# atmega2560_2_sch.net
KiCad netlist of a schematic drawn in Altium Designer
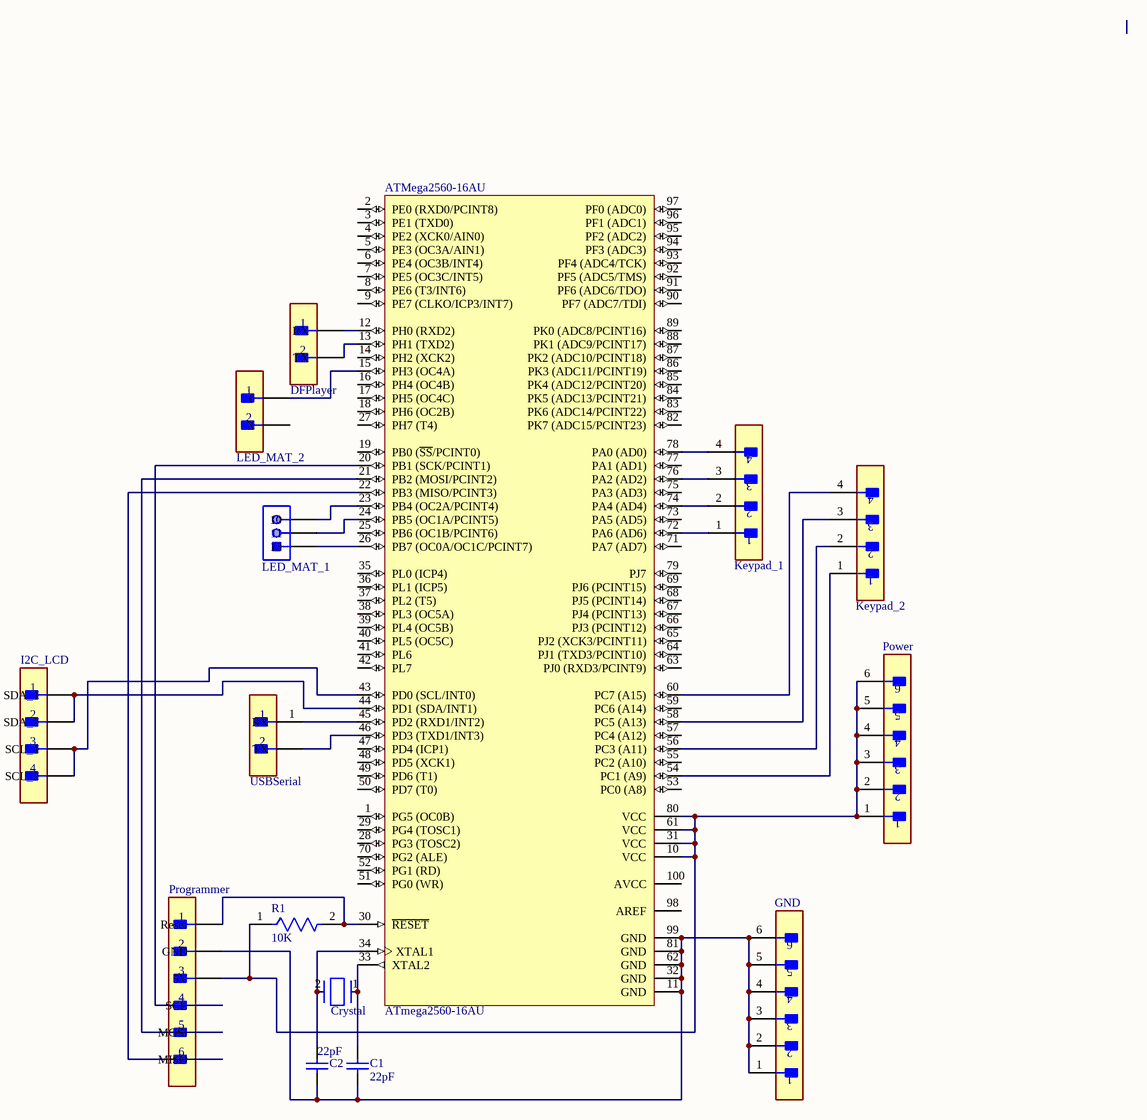
[diagram p0: atmega2560_2_sch.SchDoc]

(export (version "E")
  (design (tool "Eeschema 10.0.6"))
  (components
    (comp (ref "ATMega2560-16AU")
      (value "ATmega2560-16AU")
      (footprint "100A_M")
      (libsource (lib "Altium Content Vault") (part "MC-8B-ATM640-SQ100"))
    )
    (comp (ref "C1")
      (value "22pF")
      (footprint "KEMT-C315-THT-2")
      (description "Capacitor, Ceramic, 22 pF, +/-10 %, 100 V, -55 to 125 degC, 2-Pin THD, RoHS, Bulk")
      (libsource (lib "Altium Content Vault") (part "CAP-NP-2"))
    )
    (comp (ref "C2")
      (value "22pF")
      (footprint "KEMT-C315-THT-2")
      (description "Capacitor, Ceramic, 22 pF, +/-10 %, 100 V, -55 to 125 degC, 2-Pin THD, RoHS, Bulk")
      (libsource (lib "Altium Content Vault") (part "CAP-NP-2"))
    )
    (comp (ref "Crystal")
      (value "ABLS-16.000MHZ-K4T")
      (footprint "FP-ABLS-MFG")
      (description "CRYSTAL 16.0000MHZ 18PF SMD")
      (fields
        (field (name "TOLERANCE") "30ppm")
        (field (name "OCTOPART") "https://octopart.com/abls-16.000mhz-k4t-abracon-18618626")
      )
      (libsource (lib "Altium Content Vault") (part "c23a69dc6c9e2f18f2079038eb95dd1"))
    )
    (comp (ref "DFPlayer")
      (value "M20-9990246")
      (footprint "FP-M20-9990246-MFG")
      (description "CONN HEADER VERT 2POS 2.54MM")
      (fields
        (field (name "OCTOPART") "https://octopart.com/m20-9990246-harwin-2590635")
        (field (name "MANUFACTURER") "Harwin")
      )
      (libsource (lib "Altium Content Vault") (part "3bc925449376181038e59eaffc5286c"))
    )
    (comp (ref "GND")
      (value "22-04-1061")
      (footprint "FP-22-04-1061-MFG")
      (description "CONN HEADER VERT 6POS 2.5MM")
      (libsource (lib "") (part "f2cb566baf1c37ab5a3b8e90bbeafd6_1"))
    )
    (comp (ref "I2C_LCD")
      (value "B4B-XH-A(LF)(SN)")
      (footprint "FP-B4B-XH-A_LF_SN-MFG")
      (description "CONN HEADER VERT 4POS 2.5MM")
      (libsource (lib "Altium Content Vault") (part "299a8cea1bdcbc3624fe62c390fa72c"))
    )
    (comp (ref "Keypad_1")
      (value "B4B-XH-A(LF)(SN)")
      (footprint "FP-B4B-XH-A_LF_SN-MFG")
      (description "CONN HEADER VERT 4POS 2.5MM")
      (libsource (lib "") (part "299a8cea1bdcbc3624fe62c390fa72c_1"))
    )
    (comp (ref "Keypad_2")
      (value "B4B-XH-A(LF)(SN)")
      (footprint "FP-B4B-XH-A_LF_SN-MFG")
      (description "CONN HEADER VERT 4POS 2.5MM")
      (libsource (lib "") (part "299a8cea1bdcbc3624fe62c390fa72c_1"))
    )
    (comp (ref "LED_MAT_1")
      (value "B3P-VH(LF)(SN)")
      (footprint "JST-B3P-VH(LF)(SN)-3_V")
      (libsource (lib "Altium Content Vault") (part "CN-1P-M-R3"))
    )
    (comp (ref "LED_MAT_2")
      (value "M20-9990246")
      (footprint "FP-M20-9990246-MFG")
      (description "CONN HEADER VERT 2POS 2.54MM")
      (fields
        (field (name "OCTOPART") "https://octopart.com/m20-9990246-harwin-2590635")
        (field (name "MANUFACTURER") "Harwin")
      )
      (libsource (lib "Altium Content Vault") (part "3bc925449376181038e59eaffc5286c"))
    )
    (comp (ref "Power")
      (value "22-04-1061")
      (footprint "FP-22-04-1061-MFG")
      (description "CONN HEADER VERT 6POS 2.5MM")
      (libsource (lib "") (part "f2cb566baf1c37ab5a3b8e90bbeafd6_1"))
    )
    (comp (ref "Programmer")
      (value "22-29-2061")
      (footprint "FP-22-29-2061-MFG")
      (description "CONN HEADER VERT 6POS 2.54MM")
      (libsource (lib "Altium Content Vault") (part "f2cb566baf1c37ab5a3b8e90bbeafd6"))
    )
    (comp (ref "R1")
      (value "10K")
      (footprint "FP-MBB0207-MFG")
      (description "RES 10K OHM 0.6W 1% AXIAL")
      (fields (field (name "TOLERANCE") "1%"))
      (libsource (lib "Altium Content Vault") (part "1029c3af85768c4190bb7ad29bc67b5"))
    )
    (comp (ref "USBSerial")
      (value "M20-9990246")
      (footprint "FP-M20-9990246-MFG")
      (description "CONN HEADER VERT 2POS 2.54MM")
      (fields
        (field (name "OCTOPART") "https://octopart.com/m20-9990246-harwin-2590635")
        (field (name "MANUFACTURER") "Harwin")
      )
      (libsource (lib "") (part "3bc925449376181038e59eaffc5286c_1"))
    )
  )
  (nets
    (net (code "1") (name "Net-(ATMega2560-16AU-PA0_(AD0))") (class "Default")
      (node (ref "ATMega2560-16AU") (pin "78") (pinfunction "PA0_(AD0)_78") (pintype "bidirectional"))
      (node (ref "Keypad_1") (pin "4") (pinfunction "4_4") (pintype "passive"))
    )
    (net (code "2") (name "Net-(ATMega2560-16AU-PA2_(AD2))") (class "Default")
      (node (ref "ATMega2560-16AU") (pin "76") (pinfunction "PA2_(AD2)_76") (pintype "bidirectional"))
      (node (ref "Keypad_1") (pin "3") (pinfunction "3_3") (pintype "passive"))
    )
    (net (code "3") (name "Net-(ATMega2560-16AU-PA4_(AD4))") (class "Default")
      (node (ref "ATMega2560-16AU") (pin "74") (pinfunction "PA4_(AD4)_74") (pintype "bidirectional"))
      (node (ref "Keypad_1") (pin "2") (pinfunction "2_2") (pintype "passive"))
    )
    (net (code "4") (name "Net-(ATMega2560-16AU-PA6_(AD6))") (class "Default")
      (node (ref "ATMega2560-16AU") (pin "72") (pinfunction "PA6_(AD6)_72") (pintype "bidirectional"))
      (node (ref "Keypad_1") (pin "1") (pinfunction "1_1") (pintype "passive"))
    )
    (net (code "5") (name "Net-(ATMega2560-16AU-PB1_(SCK{slash}PCINT1))") (class "Default")
      (node (ref "ATMega2560-16AU") (pin "20") (pinfunction "PB1_(SCK/PCINT1)_20") (pintype "bidirectional"))
      (node (ref "Programmer") (pin "4") (pinfunction "SCL_4") (pintype "passive"))
    )
    (net (code "6") (name "Net-(ATMega2560-16AU-PB2_(MOSI{slash}PCINT2))") (class "Default")
      (node (ref "ATMega2560-16AU") (pin "21") (pinfunction "PB2_(MOSI/PCINT2)_21") (pintype "bidirectional"))
      (node (ref "Programmer") (pin "5") (pinfunction "MOSI_5") (pintype "passive"))
    )
    (net (code "7") (name "Net-(ATMega2560-16AU-PB3_(MISO{slash}PCINT3))") (class "Default")
      (node (ref "ATMega2560-16AU") (pin "22") (pinfunction "PB3_(MISO/PCINT3)_22") (pintype "bidirectional"))
      (node (ref "Programmer") (pin "6") (pinfunction "MISO_6") (pintype "passive"))
    )
    (net (code "8") (name "Net-(ATMega2560-16AU-PB4_(OC2A{slash}PCINT4))") (class "Default")
      (node (ref "ATMega2560-16AU") (pin "23") (pinfunction "PB4_(OC2A/PCINT4)_23") (pintype "bidirectional"))
      (node (ref "LED_MAT_1") (pin "3") (pinfunction "10_3") (pintype "passive"))
    )
    (net (code "9") (name "Net-(ATMega2560-16AU-PB5_(OC1A{slash}PCINT5))") (class "Default")
      (node (ref "ATMega2560-16AU") (pin "24") (pinfunction "PB5_(OC1A/PCINT5)_24") (pintype "bidirectional"))
      (node (ref "LED_MAT_1") (pin "2") (pinfunction "11_2") (pintype "passive"))
    )
    (net (code "10") (name "Net-(ATMega2560-16AU-PB7_(OC0A{slash}OC1C{slash}PCINT7))") (class "Default")
      (node (ref "ATMega2560-16AU") (pin "26") (pinfunction "PB7_(OC0A/OC1C/PCINT7)_26") (pintype "bidirectional"))
      (node (ref "LED_MAT_1") (pin "1") (pinfunction "13_1") (pintype "passive"))
    )
    (net (code "11") (name "Net-(ATMega2560-16AU-PC1_(A9))") (class "Default")
      (node (ref "ATMega2560-16AU") (pin "54") (pinfunction "PC1_(A9)_54") (pintype "bidirectional"))
      (node (ref "Keypad_2") (pin "1") (pinfunction "1_1") (pintype "passive"))
    )
    (net (code "12") (name "Net-(ATMega2560-16AU-PC3_(A11))") (class "Default")
      (node (ref "ATMega2560-16AU") (pin "56") (pinfunction "PC3_(A11)_56") (pintype "bidirectional"))
      (node (ref "Keypad_2") (pin "2") (pinfunction "2_2") (pintype "passive"))
    )
    (net (code "13") (name "Net-(ATMega2560-16AU-PC5_(A13))") (class "Default")
      (node (ref "ATMega2560-16AU") (pin "58") (pinfunction "PC5_(A13)_58") (pintype "bidirectional"))
      (node (ref "Keypad_2") (pin "3") (pinfunction "3_3") (pintype "passive"))
    )
    (net (code "14") (name "Net-(ATMega2560-16AU-PC7_(A15))") (class "Default")
      (node (ref "ATMega2560-16AU") (pin "60") (pinfunction "PC7_(A15)_60") (pintype "bidirectional"))
      (node (ref "Keypad_2") (pin "4") (pinfunction "4_4") (pintype "passive"))
    )
    (net (code "15") (name "Net-(ATMega2560-16AU-PD0_(SCL{slash}INT0))") (class "Default")
      (node (ref "ATMega2560-16AU") (pin "43") (pinfunction "PD0_(SCL/INT0)_43") (pintype "bidirectional"))
      (node (ref "I2C_LCD") (pin "3") (pinfunction "SCL_1_3") (pintype "passive"))
      (node (ref "I2C_LCD") (pin "4") (pinfunction "SCL_2_4") (pintype "passive"))
    )
    (net (code "16") (name "Net-(ATMega2560-16AU-PD1_(SDA{slash}INT1))") (class "Default")
      (node (ref "ATMega2560-16AU") (pin "44") (pinfunction "PD1_(SDA/INT1)_44") (pintype "bidirectional"))
      (node (ref "I2C_LCD") (pin "1") (pinfunction "SDA_1_1") (pintype "passive"))
      (node (ref "I2C_LCD") (pin "2") (pinfunction "SDA_2_2") (pintype "passive"))
    )
    (net (code "17") (name "Net-(ATMega2560-16AU-PD2_(RXD1{slash}INT2))") (class "Default")
      (node (ref "ATMega2560-16AU") (pin "45") (pinfunction "PD2_(RXD1/INT2)_45") (pintype "bidirectional"))
      (node (ref "USBSerial") (pin "1") (pinfunction "RX_1") (pintype "passive"))
    )
    (net (code "18") (name "Net-(ATMega2560-16AU-PD3_(TXD1{slash}INT3))") (class "Default")
      (node (ref "ATMega2560-16AU") (pin "46") (pinfunction "PD3_(TXD1/INT3)_46") (pintype "bidirectional"))
      (node (ref "USBSerial") (pin "2") (pinfunction "TX_2") (pintype "passive"))
    )
    (net (code "19") (name "Net-(ATMega2560-16AU-PH0_(RXD2))") (class "Default")
      (node (ref "ATMega2560-16AU") (pin "12") (pinfunction "PH0_(RXD2)_12") (pintype "bidirectional"))
      (node (ref "DFPlayer") (pin "1") (pinfunction "RX_1") (pintype "passive"))
    )
    (net (code "20") (name "Net-(ATMega2560-16AU-PH1_(TXD2))") (class "Default")
      (node (ref "ATMega2560-16AU") (pin "13") (pinfunction "PH1_(TXD2)_13") (pintype "bidirectional"))
      (node (ref "DFPlayer") (pin "2") (pinfunction "TX_2") (pintype "passive"))
    )
    (net (code "21") (name "Net-(ATMega2560-16AU-PH3_(OC4A))") (class "Default")
      (node (ref "ATMega2560-16AU") (pin "15") (pinfunction "PH3_(OC4A)_15") (pintype "bidirectional"))
      (node (ref "LED_MAT_2") (pin "1") (pinfunction "RX_1") (pintype "passive"))
    )
    (net (code "22") (name "Net-(ATMega2560-16AU-XTAL1)") (class "Default")
      (node (ref "ATMega2560-16AU") (pin "34") (pinfunction "XTAL1_34") (pintype "input"))
      (node (ref "C2") (pin "2") (pinfunction "2_2") (pintype "passive"))
      (node (ref "Crystal") (pin "2") (pinfunction "2_2") (pintype "passive"))
    )
    (net (code "23") (name "Net-(ATMega2560-16AU-XTAL2)") (class "Default")
      (node (ref "ATMega2560-16AU") (pin "33") (pinfunction "XTAL2_33") (pintype "output"))
      (node (ref "C1") (pin "2") (pinfunction "2_2") (pintype "passive"))
      (node (ref "Crystal") (pin "1") (pinfunction "1_1") (pintype "passive"))
    )
    (net (code "24") (name "Net-(ATMega2560-16AU-~{RESET})") (class "Default")
      (node (ref "ATMega2560-16AU") (pin "30") (pinfunction "~{RESET}_30") (pintype "input"))
      (node (ref "Programmer") (pin "1") (pinfunction "Reset_1") (pintype "passive"))
      (node (ref "R1") (pin "2") (pinfunction "2_2") (pintype "passive"))
    )
    (net (code "25") (name "Net-(Programmer-5V)") (class "Default")
      (node (ref "ATMega2560-16AU") (pin "10") (pinfunction "VCC_10") (pintype "power_in"))
      (node (ref "ATMega2560-16AU") (pin "31") (pinfunction "VCC_31") (pintype "power_in"))
      (node (ref "ATMega2560-16AU") (pin "61") (pinfunction "VCC_61") (pintype "power_in"))
      (node (ref "ATMega2560-16AU") (pin "80") (pinfunction "VCC_80") (pintype "power_in"))
      (node (ref "Power") (pin "1") (pinfunction "1_1") (pintype "passive"))
      (node (ref "Power") (pin "2") (pinfunction "2_2") (pintype "passive"))
      (node (ref "Power") (pin "3") (pinfunction "3_3") (pintype "passive"))
      (node (ref "Power") (pin "4") (pinfunction "4_4") (pintype "passive"))
      (node (ref "Power") (pin "5") (pinfunction "5_5") (pintype "passive"))
      (node (ref "Power") (pin "6") (pinfunction "6_6") (pintype "passive"))
      (node (ref "Programmer") (pin "3") (pinfunction "5V_3") (pintype "passive"))
      (node (ref "R1") (pin "1") (pinfunction "1_1") (pintype "passive"))
    )
    (net (code "26") (name "Net-(Programmer-GND)") (class "Default")
      (node (ref "ATMega2560-16AU") (pin "11") (pinfunction "GND_11") (pintype "power_in"))
      (node (ref "ATMega2560-16AU") (pin "32") (pinfunction "GND_32") (pintype "power_in"))
      (node (ref "ATMega2560-16AU") (pin "62") (pinfunction "GND_62") (pintype "power_in"))
      (node (ref "ATMega2560-16AU") (pin "81") (pinfunction "GND_81") (pintype "power_in"))
      (node (ref "ATMega2560-16AU") (pin "99") (pinfunction "GND_99") (pintype "power_in"))
      (node (ref "C1") (pin "1") (pinfunction "1_1") (pintype "passive"))
      (node (ref "C2") (pin "1") (pinfunction "1_1") (pintype "passive"))
      (node (ref "GND") (pin "1") (pinfunction "1_1") (pintype "passive"))
      (node (ref "GND") (pin "2") (pinfunction "2_2") (pintype "passive"))
      (node (ref "GND") (pin "3") (pinfunction "3_3") (pintype "passive"))
      (node (ref "GND") (pin "4") (pinfunction "4_4") (pintype "passive"))
      (node (ref "GND") (pin "5") (pinfunction "5_5") (pintype "passive"))
      (node (ref "GND") (pin "6") (pinfunction "6_6") (pintype "passive"))
      (node (ref "Programmer") (pin "2") (pinfunction "GND_2") (pintype "passive"))
    )
    (net (code "27") (name "unconnected-(ATMega2560-16AU-AREF-Pad98)") (class "Default")
      (node (ref "ATMega2560-16AU") (pin "98") (pinfunction "AREF_98") (pintype "power_in"))
    )
    (net (code "28") (name "unconnected-(ATMega2560-16AU-AVCC-Pad100)") (class "Default")
      (node (ref "ATMega2560-16AU") (pin "100") (pinfunction "AVCC_100") (pintype "power_in"))
    )
    (net (code "29") (name "unconnected-(ATMega2560-16AU-PA1_(AD1)-Pad77)") (class "Default")
      (node (ref "ATMega2560-16AU") (pin "77") (pinfunction "PA1_(AD1)_77") (pintype "bidirectional"))
    )
    (net (code "30") (name "unconnected-(ATMega2560-16AU-PA3_(AD3)-Pad75)") (class "Default")
      (node (ref "ATMega2560-16AU") (pin "75") (pinfunction "PA3_(AD3)_75") (pintype "bidirectional"))
    )
    (net (code "31") (name "unconnected-(ATMega2560-16AU-PA5_(AD5)-Pad73)") (class "Default")
      (node (ref "ATMega2560-16AU") (pin "73") (pinfunction "PA5_(AD5)_73") (pintype "bidirectional"))
    )
    (net (code "32") (name "unconnected-(ATMega2560-16AU-PA7_(AD7)-Pad71)") (class "Default")
      (node (ref "ATMega2560-16AU") (pin "71") (pinfunction "PA7_(AD7)_71") (pintype "bidirectional"))
    )
    (net (code "33") (name "unconnected-(ATMega2560-16AU-PB0_(~{SS}{slash}PCINT0)-Pad19)") (class "Default")
      (node (ref "ATMega2560-16AU") (pin "19") (pinfunction "PB0_(~{SS}/PCINT0)_19") (pintype "bidirectional"))
    )
    (net (code "34") (name "unconnected-(ATMega2560-16AU-PB6_(OC1B{slash}PCINT6)-Pad25)") (class "Default")
      (node (ref "ATMega2560-16AU") (pin "25") (pinfunction "PB6_(OC1B/PCINT6)_25") (pintype "bidirectional"))
    )
    (net (code "35") (name "unconnected-(ATMega2560-16AU-PC0_(A8)-Pad53)") (class "Default")
      (node (ref "ATMega2560-16AU") (pin "53") (pinfunction "PC0_(A8)_53") (pintype "bidirectional"))
    )
    (net (code "36") (name "unconnected-(ATMega2560-16AU-PC2_(A10)-Pad55)") (class "Default")
      (node (ref "ATMega2560-16AU") (pin "55") (pinfunction "PC2_(A10)_55") (pintype "bidirectional"))
    )
    (net (code "37") (name "unconnected-(ATMega2560-16AU-PC4_(A12)-Pad57)") (class "Default")
      (node (ref "ATMega2560-16AU") (pin "57") (pinfunction "PC4_(A12)_57") (pintype "bidirectional"))
    )
    (net (code "38") (name "unconnected-(ATMega2560-16AU-PC6_(A14)-Pad59)") (class "Default")
      (node (ref "ATMega2560-16AU") (pin "59") (pinfunction "PC6_(A14)_59") (pintype "bidirectional"))
    )
    (net (code "39") (name "unconnected-(ATMega2560-16AU-PD4_(ICP1)-Pad47)") (class "Default")
      (node (ref "ATMega2560-16AU") (pin "47") (pinfunction "PD4_(ICP1)_47") (pintype "bidirectional"))
    )
    (net (code "40") (name "unconnected-(ATMega2560-16AU-PD5_(XCK1)-Pad48)") (class "Default")
      (node (ref "ATMega2560-16AU") (pin "48") (pinfunction "PD5_(XCK1)_48") (pintype "bidirectional"))
    )
    (net (code "41") (name "unconnected-(ATMega2560-16AU-PD6_(T1)-Pad49)") (class "Default")
      (node (ref "ATMega2560-16AU") (pin "49") (pinfunction "PD6_(T1)_49") (pintype "bidirectional"))
    )
    (net (code "42") (name "unconnected-(ATMega2560-16AU-PD7_(T0)-Pad50)") (class "Default")
      (node (ref "ATMega2560-16AU") (pin "50") (pinfunction "PD7_(T0)_50") (pintype "bidirectional"))
    )
    (net (code "43") (name "unconnected-(ATMega2560-16AU-PE0_(RXD0{slash}PCINT8)-Pad2)") (class "Default")
      (node (ref "ATMega2560-16AU") (pin "2") (pinfunction "PE0_(RXD0/PCINT8)_2") (pintype "bidirectional"))
    )
    (net (code "44") (name "unconnected-(ATMega2560-16AU-PE1_(TXD0)-Pad3)") (class "Default")
      (node (ref "ATMega2560-16AU") (pin "3") (pinfunction "PE1_(TXD0)_3") (pintype "bidirectional"))
    )
    (net (code "45") (name "unconnected-(ATMega2560-16AU-PE2_(XCK0{slash}AIN0)-Pad4)") (class "Default")
      (node (ref "ATMega2560-16AU") (pin "4") (pinfunction "PE2_(XCK0/AIN0)_4") (pintype "bidirectional"))
    )
    (net (code "46") (name "unconnected-(ATMega2560-16AU-PE3_(OC3A{slash}AIN1)-Pad5)") (class "Default")
      (node (ref "ATMega2560-16AU") (pin "5") (pinfunction "PE3_(OC3A/AIN1)_5") (pintype "bidirectional"))
    )
    (net (code "47") (name "unconnected-(ATMega2560-16AU-PE4_(OC3B{slash}INT4)-Pad6)") (class "Default")
      (node (ref "ATMega2560-16AU") (pin "6") (pinfunction "PE4_(OC3B/INT4)_6") (pintype "bidirectional"))
    )
    (net (code "48") (name "unconnected-(ATMega2560-16AU-PE5_(OC3C{slash}INT5)-Pad7)") (class "Default")
      (node (ref "ATMega2560-16AU") (pin "7") (pinfunction "PE5_(OC3C/INT5)_7") (pintype "bidirectional"))
    )
    (net (code "49") (name "unconnected-(ATMega2560-16AU-PE6_(T3{slash}INT6)-Pad8)") (class "Default")
      (node (ref "ATMega2560-16AU") (pin "8") (pinfunction "PE6_(T3/INT6)_8") (pintype "bidirectional"))
    )
    (net (code "50") (name "unconnected-(ATMega2560-16AU-PE7_(CLKO{slash}ICP3{slash}INT7)-Pad9)") (class "Default")
      (node (ref "ATMega2560-16AU") (pin "9") (pinfunction "PE7_(CLKO/ICP3/INT7)_9") (pintype "bidirectional"))
    )
    (net (code "51") (name "unconnected-(ATMega2560-16AU-PF0_(ADC0)-Pad97)") (class "Default")
      (node (ref "ATMega2560-16AU") (pin "97") (pinfunction "PF0_(ADC0)_97") (pintype "bidirectional"))
    )
    (net (code "52") (name "unconnected-(ATMega2560-16AU-PF1_(ADC1)-Pad96)") (class "Default")
      (node (ref "ATMega2560-16AU") (pin "96") (pinfunction "PF1_(ADC1)_96") (pintype "bidirectional"))
    )
    (net (code "53") (name "unconnected-(ATMega2560-16AU-PF2_(ADC2)-Pad95)") (class "Default")
      (node (ref "ATMega2560-16AU") (pin "95") (pinfunction "PF2_(ADC2)_95") (pintype "bidirectional"))
    )
    (net (code "54") (name "unconnected-(ATMega2560-16AU-PF3_(ADC3)-Pad94)") (class "Default")
      (node (ref "ATMega2560-16AU") (pin "94") (pinfunction "PF3_(ADC3)_94") (pintype "bidirectional"))
    )
    (net (code "55") (name "unconnected-(ATMega2560-16AU-PF4_(ADC4{slash}TCK)-Pad93)") (class "Default")
      (node (ref "ATMega2560-16AU") (pin "93") (pinfunction "PF4_(ADC4/TCK)_93") (pintype "bidirectional"))
    )
    (net (code "56") (name "unconnected-(ATMega2560-16AU-PF5_(ADC5{slash}TMS)-Pad92)") (class "Default")
      (node (ref "ATMega2560-16AU") (pin "92") (pinfunction "PF5_(ADC5/TMS)_92") (pintype "bidirectional"))
    )
    (net (code "57") (name "unconnected-(ATMega2560-16AU-PF6_(ADC6{slash}TDO)-Pad91)") (class "Default")
      (node (ref "ATMega2560-16AU") (pin "91") (pinfunction "PF6_(ADC6/TDO)_91") (pintype "bidirectional"))
    )
    (net (code "58") (name "unconnected-(ATMega2560-16AU-PF7_(ADC7{slash}TDI)-Pad90)") (class "Default")
      (node (ref "ATMega2560-16AU") (pin "90") (pinfunction "PF7_(ADC7/TDI)_90") (pintype "bidirectional"))
    )
    (net (code "59") (name "unconnected-(ATMega2560-16AU-PG0_(WR)-Pad51)") (class "Default")
      (node (ref "ATMega2560-16AU") (pin "51") (pinfunction "PG0_(WR)_51") (pintype "bidirectional"))
    )
    (net (code "60") (name "unconnected-(ATMega2560-16AU-PG1_(RD)-Pad52)") (class "Default")
      (node (ref "ATMega2560-16AU") (pin "52") (pinfunction "PG1_(RD)_52") (pintype "bidirectional"))
    )
    (net (code "61") (name "unconnected-(ATMega2560-16AU-PG2_(ALE)-Pad70)") (class "Default")
      (node (ref "ATMega2560-16AU") (pin "70") (pinfunction "PG2_(ALE)_70") (pintype "bidirectional"))
    )
    (net (code "62") (name "unconnected-(ATMega2560-16AU-PG3_(TOSC2)-Pad28)") (class "Default")
      (node (ref "ATMega2560-16AU") (pin "28") (pinfunction "PG3_(TOSC2)_28") (pintype "bidirectional"))
    )
    (net (code "63") (name "unconnected-(ATMega2560-16AU-PG4_(TOSC1)-Pad29)") (class "Default")
      (node (ref "ATMega2560-16AU") (pin "29") (pinfunction "PG4_(TOSC1)_29") (pintype "bidirectional"))
    )
    (net (code "64") (name "unconnected-(ATMega2560-16AU-PG5_(OC0B)-Pad1)") (class "Default")
      (node (ref "ATMega2560-16AU") (pin "1") (pinfunction "PG5_(OC0B)_1") (pintype "bidirectional"))
    )
    (net (code "65") (name "unconnected-(ATMega2560-16AU-PH2_(XCK2)-Pad14)") (class "Default")
      (node (ref "ATMega2560-16AU") (pin "14") (pinfunction "PH2_(XCK2)_14") (pintype "bidirectional"))
    )
    (net (code "66") (name "unconnected-(ATMega2560-16AU-PH4_(OC4B)-Pad16)") (class "Default")
      (node (ref "ATMega2560-16AU") (pin "16") (pinfunction "PH4_(OC4B)_16") (pintype "bidirectional"))
    )
    (net (code "67") (name "unconnected-(ATMega2560-16AU-PH5_(OC4C)-Pad17)") (class "Default")
      (node (ref "ATMega2560-16AU") (pin "17") (pinfunction "PH5_(OC4C)_17") (pintype "bidirectional"))
    )
    (net (code "68") (name "unconnected-(ATMega2560-16AU-PH6_(OC2B)-Pad18)") (class "Default")
      (node (ref "ATMega2560-16AU") (pin "18") (pinfunction "PH6_(OC2B)_18") (pintype "bidirectional"))
    )
    (net (code "69") (name "unconnected-(ATMega2560-16AU-PH7_(T4)-Pad27)") (class "Default")
      (node (ref "ATMega2560-16AU") (pin "27") (pinfunction "PH7_(T4)_27") (pintype "bidirectional"))
    )
    (net (code "70") (name "unconnected-(ATMega2560-16AU-PJ0_(RXD3{slash}PCINT9)-Pad63)") (class "Default")
      (node (ref "ATMega2560-16AU") (pin "63") (pinfunction "PJ0_(RXD3/PCINT9)_63") (pintype "bidirectional"))
    )
    (net (code "71") (name "unconnected-(ATMega2560-16AU-PJ1_(TXD3{slash}PCINT10)-Pad64)") (class "Default")
      (node (ref "ATMega2560-16AU") (pin "64") (pinfunction "PJ1_(TXD3/PCINT10)_64") (pintype "bidirectional"))
    )
    (net (code "72") (name "unconnected-(ATMega2560-16AU-PJ2_(XCK3{slash}PCINT11)-Pad65)") (class "Default")
      (node (ref "ATMega2560-16AU") (pin "65") (pinfunction "PJ2_(XCK3/PCINT11)_65") (pintype "bidirectional"))
    )
    (net (code "73") (name "unconnected-(ATMega2560-16AU-PJ3_(PCINT12)-Pad66)") (class "Default")
      (node (ref "ATMega2560-16AU") (pin "66") (pinfunction "PJ3_(PCINT12)_66") (pintype "bidirectional"))
    )
    (net (code "74") (name "unconnected-(ATMega2560-16AU-PJ4_(PCINT13)-Pad67)") (class "Default")
      (node (ref "ATMega2560-16AU") (pin "67") (pinfunction "PJ4_(PCINT13)_67") (pintype "bidirectional"))
    )
    (net (code "75") (name "unconnected-(ATMega2560-16AU-PJ5_(PCINT14)-Pad68)") (class "Default")
      (node (ref "ATMega2560-16AU") (pin "68") (pinfunction "PJ5_(PCINT14)_68") (pintype "bidirectional"))
    )
    (net (code "76") (name "unconnected-(ATMega2560-16AU-PJ6_(PCINT15)-Pad69)") (class "Default")
      (node (ref "ATMega2560-16AU") (pin "69") (pinfunction "PJ6_(PCINT15)_69") (pintype "bidirectional"))
    )
    (net (code "77") (name "unconnected-(ATMega2560-16AU-PJ7-Pad79)") (class "Default")
      (node (ref "ATMega2560-16AU") (pin "79") (pinfunction "PJ7_79") (pintype "bidirectional"))
    )
    (net (code "78") (name "unconnected-(ATMega2560-16AU-PK0_(ADC8{slash}PCINT16)-Pad89)") (class "Default")
      (node (ref "ATMega2560-16AU") (pin "89") (pinfunction "PK0_(ADC8/PCINT16)_89") (pintype "bidirectional"))
    )
    (net (code "79") (name "unconnected-(ATMega2560-16AU-PK1_(ADC9{slash}PCINT17)-Pad88)") (class "Default")
      (node (ref "ATMega2560-16AU") (pin "88") (pinfunction "PK1_(ADC9/PCINT17)_88") (pintype "bidirectional"))
    )
    (net (code "80") (name "unconnected-(ATMega2560-16AU-PK2_(ADC10{slash}PCINT18)-Pad87)") (class "Default")
      (node (ref "ATMega2560-16AU") (pin "87") (pinfunction "PK2_(ADC10/PCINT18)_87") (pintype "bidirectional"))
    )
    (net (code "81") (name "unconnected-(ATMega2560-16AU-PK3_(ADC11{slash}PCINT19)-Pad86)") (class "Default")
      (node (ref "ATMega2560-16AU") (pin "86") (pinfunction "PK3_(ADC11/PCINT19)_86") (pintype "bidirectional"))
    )
    (net (code "82") (name "unconnected-(ATMega2560-16AU-PK4_(ADC12{slash}PCINT20)-Pad85)") (class "Default")
      (node (ref "ATMega2560-16AU") (pin "85") (pinfunction "PK4_(ADC12/PCINT20)_85") (pintype "bidirectional"))
    )
    (net (code "83") (name "unconnected-(ATMega2560-16AU-PK5_(ADC13{slash}PCINT21)-Pad84)") (class "Default")
      (node (ref "ATMega2560-16AU") (pin "84") (pinfunction "PK5_(ADC13/PCINT21)_84") (pintype "bidirectional"))
    )
    (net (code "84") (name "unconnected-(ATMega2560-16AU-PK6_(ADC14{slash}PCINT22)-Pad83)") (class "Default")
      (node (ref "ATMega2560-16AU") (pin "83") (pinfunction "PK6_(ADC14/PCINT22)_83") (pintype "bidirectional"))
    )
    (net (code "85") (name "unconnected-(ATMega2560-16AU-PK7_(ADC15{slash}PCINT23)-Pad82)") (class "Default")
      (node (ref "ATMega2560-16AU") (pin "82") (pinfunction "PK7_(ADC15/PCINT23)_82") (pintype "bidirectional"))
    )
    (net (code "86") (name "unconnected-(ATMega2560-16AU-PL0_(ICP4)-Pad35)") (class "Default")
      (node (ref "ATMega2560-16AU") (pin "35") (pinfunction "PL0_(ICP4)_35") (pintype "bidirectional"))
    )
    (net (code "87") (name "unconnected-(ATMega2560-16AU-PL1_(ICP5)-Pad36)") (class "Default")
      (node (ref "ATMega2560-16AU") (pin "36") (pinfunction "PL1_(ICP5)_36") (pintype "bidirectional"))
    )
    (net (code "88") (name "unconnected-(ATMega2560-16AU-PL2_(T5)-Pad37)") (class "Default")
      (node (ref "ATMega2560-16AU") (pin "37") (pinfunction "PL2_(T5)_37") (pintype "bidirectional"))
    )
    (net (code "89") (name "unconnected-(ATMega2560-16AU-PL3_(OC5A)-Pad38)") (class "Default")
      (node (ref "ATMega2560-16AU") (pin "38") (pinfunction "PL3_(OC5A)_38") (pintype "bidirectional"))
    )
    (net (code "90") (name "unconnected-(ATMega2560-16AU-PL4_(OC5B)-Pad39)") (class "Default")
      (node (ref "ATMega2560-16AU") (pin "39") (pinfunction "PL4_(OC5B)_39") (pintype "bidirectional"))
    )
    (net (code "91") (name "unconnected-(ATMega2560-16AU-PL5_(OC5C)-Pad40)") (class "Default")
      (node (ref "ATMega2560-16AU") (pin "40") (pinfunction "PL5_(OC5C)_40") (pintype "bidirectional"))
    )
    (net (code "92") (name "unconnected-(ATMega2560-16AU-PL6-Pad41)") (class "Default")
      (node (ref "ATMega2560-16AU") (pin "41") (pinfunction "PL6_41") (pintype "bidirectional"))
    )
    (net (code "93") (name "unconnected-(ATMega2560-16AU-PL7-Pad42)") (class "Default")
      (node (ref "ATMega2560-16AU") (pin "42") (pinfunction "PL7_42") (pintype "bidirectional"))
    )
    (net (code "94") (name "unconnected-(LED_MAT_2-TX-Pad2)") (class "Default")
      (node (ref "LED_MAT_2") (pin "2") (pinfunction "TX_2") (pintype "passive"))
    )
  )
)
